# 7Segment-Display.net
KiCad netlist of a schematic drawn in Altium Designer
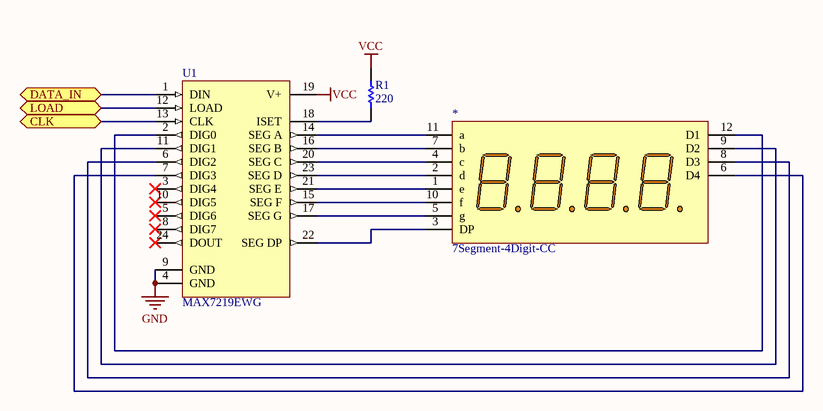
[diagram p0: 7Segment-Display.SchDoc]

(export (version "E")
  (design (tool "Eeschema 10.0.6"))
  (components
    (comp (ref "*")
      (value "7Segment-4Digit-CC")
      (footprint "7Segment-4Digit-CC")
      (libsource (lib "toko-Embedded") (part "7Segment-4Digit-CC"))
    )
    (comp (ref "R1")
      (value "220")
      (footprint "toko-Embedded:0207/10")
      (description "Resistor")
      (fields (field (name "PUBLISHER") "Altium Limited"))
      (libsource (lib "Miscellaneous Devices") (part "Res1"))
    )
    (comp (ref "U1")
      (value "MAX7219EWG")
      (footprint "WSO24_N")
      (description "Serially Interfaced, 8-Digit LED Display Driver")
      (fields (field (name "PUBLISHER") "Altium Limited"))
      (libsource (lib "Maxim Interface Display Driver") (part "MAX7219EWG"))
    )
  )
  (nets
    (net (code "1") (name "/CLK") (class "Default")
      (node (ref "U1") (pin "13") (pinfunction "CLK_13") (pintype "input"))
    )
    (net (code "2") (name "/DATA_IN") (class "Default")
      (node (ref "U1") (pin "1") (pinfunction "DIN_1") (pintype "input"))
    )
    (net (code "3") (name "/LOAD") (class "Default")
      (node (ref "U1") (pin "12") (pinfunction "LOAD_12") (pintype "input"))
    )
    (net (code "4") (name "GND") (class "Default")
      (node (ref "U1") (pin "4") (pinfunction "GND_4") (pintype "power_in"))
      (node (ref "U1") (pin "9") (pinfunction "GND_9") (pintype "power_in"))
    )
    (net (code "5") (name "Net-(*-D1)") (class "Default")
      (node (ref "*") (pin "12") (pinfunction "D1_12") (pintype "passive"))
      (node (ref "U1") (pin "2") (pinfunction "DIG0_2") (pintype "output"))
    )
    (net (code "6") (name "Net-(*-D2)") (class "Default")
      (node (ref "*") (pin "9") (pinfunction "D2_9") (pintype "passive"))
      (node (ref "U1") (pin "11") (pinfunction "DIG1_11") (pintype "output"))
    )
    (net (code "7") (name "Net-(*-D3)") (class "Default")
      (node (ref "*") (pin "8") (pinfunction "D3_8") (pintype "passive"))
      (node (ref "U1") (pin "6") (pinfunction "DIG2_6") (pintype "output"))
    )
    (net (code "8") (name "Net-(*-D4)") (class "Default")
      (node (ref "*") (pin "6") (pinfunction "D4_6") (pintype "passive"))
      (node (ref "U1") (pin "7") (pinfunction "DIG3_7") (pintype "output"))
    )
    (net (code "9") (name "Net-(*-DP)") (class "Default")
      (node (ref "*") (pin "3") (pinfunction "DP_3") (pintype "passive"))
      (node (ref "U1") (pin "22") (pinfunction "SEG_DP_22") (pintype "output"))
    )
    (net (code "10") (name "Net-(*-a)") (class "Default")
      (node (ref "*") (pin "11") (pinfunction "a_11") (pintype "passive"))
      (node (ref "U1") (pin "14") (pinfunction "SEG_A_14") (pintype "output"))
    )
    (net (code "11") (name "Net-(*-b)") (class "Default")
      (node (ref "*") (pin "7") (pinfunction "b_7") (pintype "passive"))
      (node (ref "U1") (pin "16") (pinfunction "SEG_B_16") (pintype "output"))
    )
    (net (code "12") (name "Net-(*-c)") (class "Default")
      (node (ref "*") (pin "4") (pinfunction "c_4") (pintype "passive"))
      (node (ref "U1") (pin "20") (pinfunction "SEG_C_20") (pintype "output"))
    )
    (net (code "13") (name "Net-(*-d)") (class "Default")
      (node (ref "*") (pin "2") (pinfunction "d_2") (pintype "passive"))
      (node (ref "U1") (pin "23") (pinfunction "SEG_D_23") (pintype "output"))
    )
    (net (code "14") (name "Net-(*-e)") (class "Default")
      (node (ref "*") (pin "1") (pinfunction "e_1") (pintype "passive"))
      (node (ref "U1") (pin "21") (pinfunction "SEG_E_21") (pintype "output"))
    )
    (net (code "15") (name "Net-(*-f)") (class "Default")
      (node (ref "*") (pin "10") (pinfunction "f_10") (pintype "passive"))
      (node (ref "U1") (pin "15") (pinfunction "SEG_F_15") (pintype "output"))
    )
    (net (code "16") (name "Net-(*-g)") (class "Default")
      (node (ref "*") (pin "5") (pinfunction "g_5") (pintype "passive"))
      (node (ref "U1") (pin "17") (pinfunction "SEG_G_17") (pintype "output"))
    )
    (net (code "17") (name "Net-(U1-ISET)") (class "Default")
      (node (ref "R1") (pin "2") (pinfunction "2_2") (pintype "passive"))
      (node (ref "U1") (pin "18") (pinfunction "ISET_18") (pintype "passive"))
    )
    (net (code "18") (name "VCC") (class "Default")
      (node (ref "R1") (pin "1") (pinfunction "1_1") (pintype "passive"))
      (node (ref "U1") (pin "19") (pinfunction "V+_19") (pintype "power_in"))
    )
    (net (code "19") (name "unconnected-(U1-DIG4-Pad3)") (class "Default")
      (node (ref "U1") (pin "3") (pinfunction "DIG4_3") (pintype "output+no_connect"))
    )
    (net (code "20") (name "unconnected-(U1-DIG5-Pad10)") (class "Default")
      (node (ref "U1") (pin "10") (pinfunction "DIG5_10") (pintype "output+no_connect"))
    )
    (net (code "21") (name "unconnected-(U1-DIG6-Pad5)") (class "Default")
      (node (ref "U1") (pin "5") (pinfunction "DIG6_5") (pintype "output+no_connect"))
    )
    (net (code "22") (name "unconnected-(U1-DIG7-Pad8)") (class "Default")
      (node (ref "U1") (pin "8") (pinfunction "DIG7_8") (pintype "output+no_connect"))
    )
    (net (code "23") (name "unconnected-(U1-DOUT-Pad24)") (class "Default")
      (node (ref "U1") (pin "24") (pinfunction "DOUT_24") (pintype "output+no_connect"))
    )
  )
)
